# Ver_5.net
KiCad netlist of a schematic drawn in EAGLE
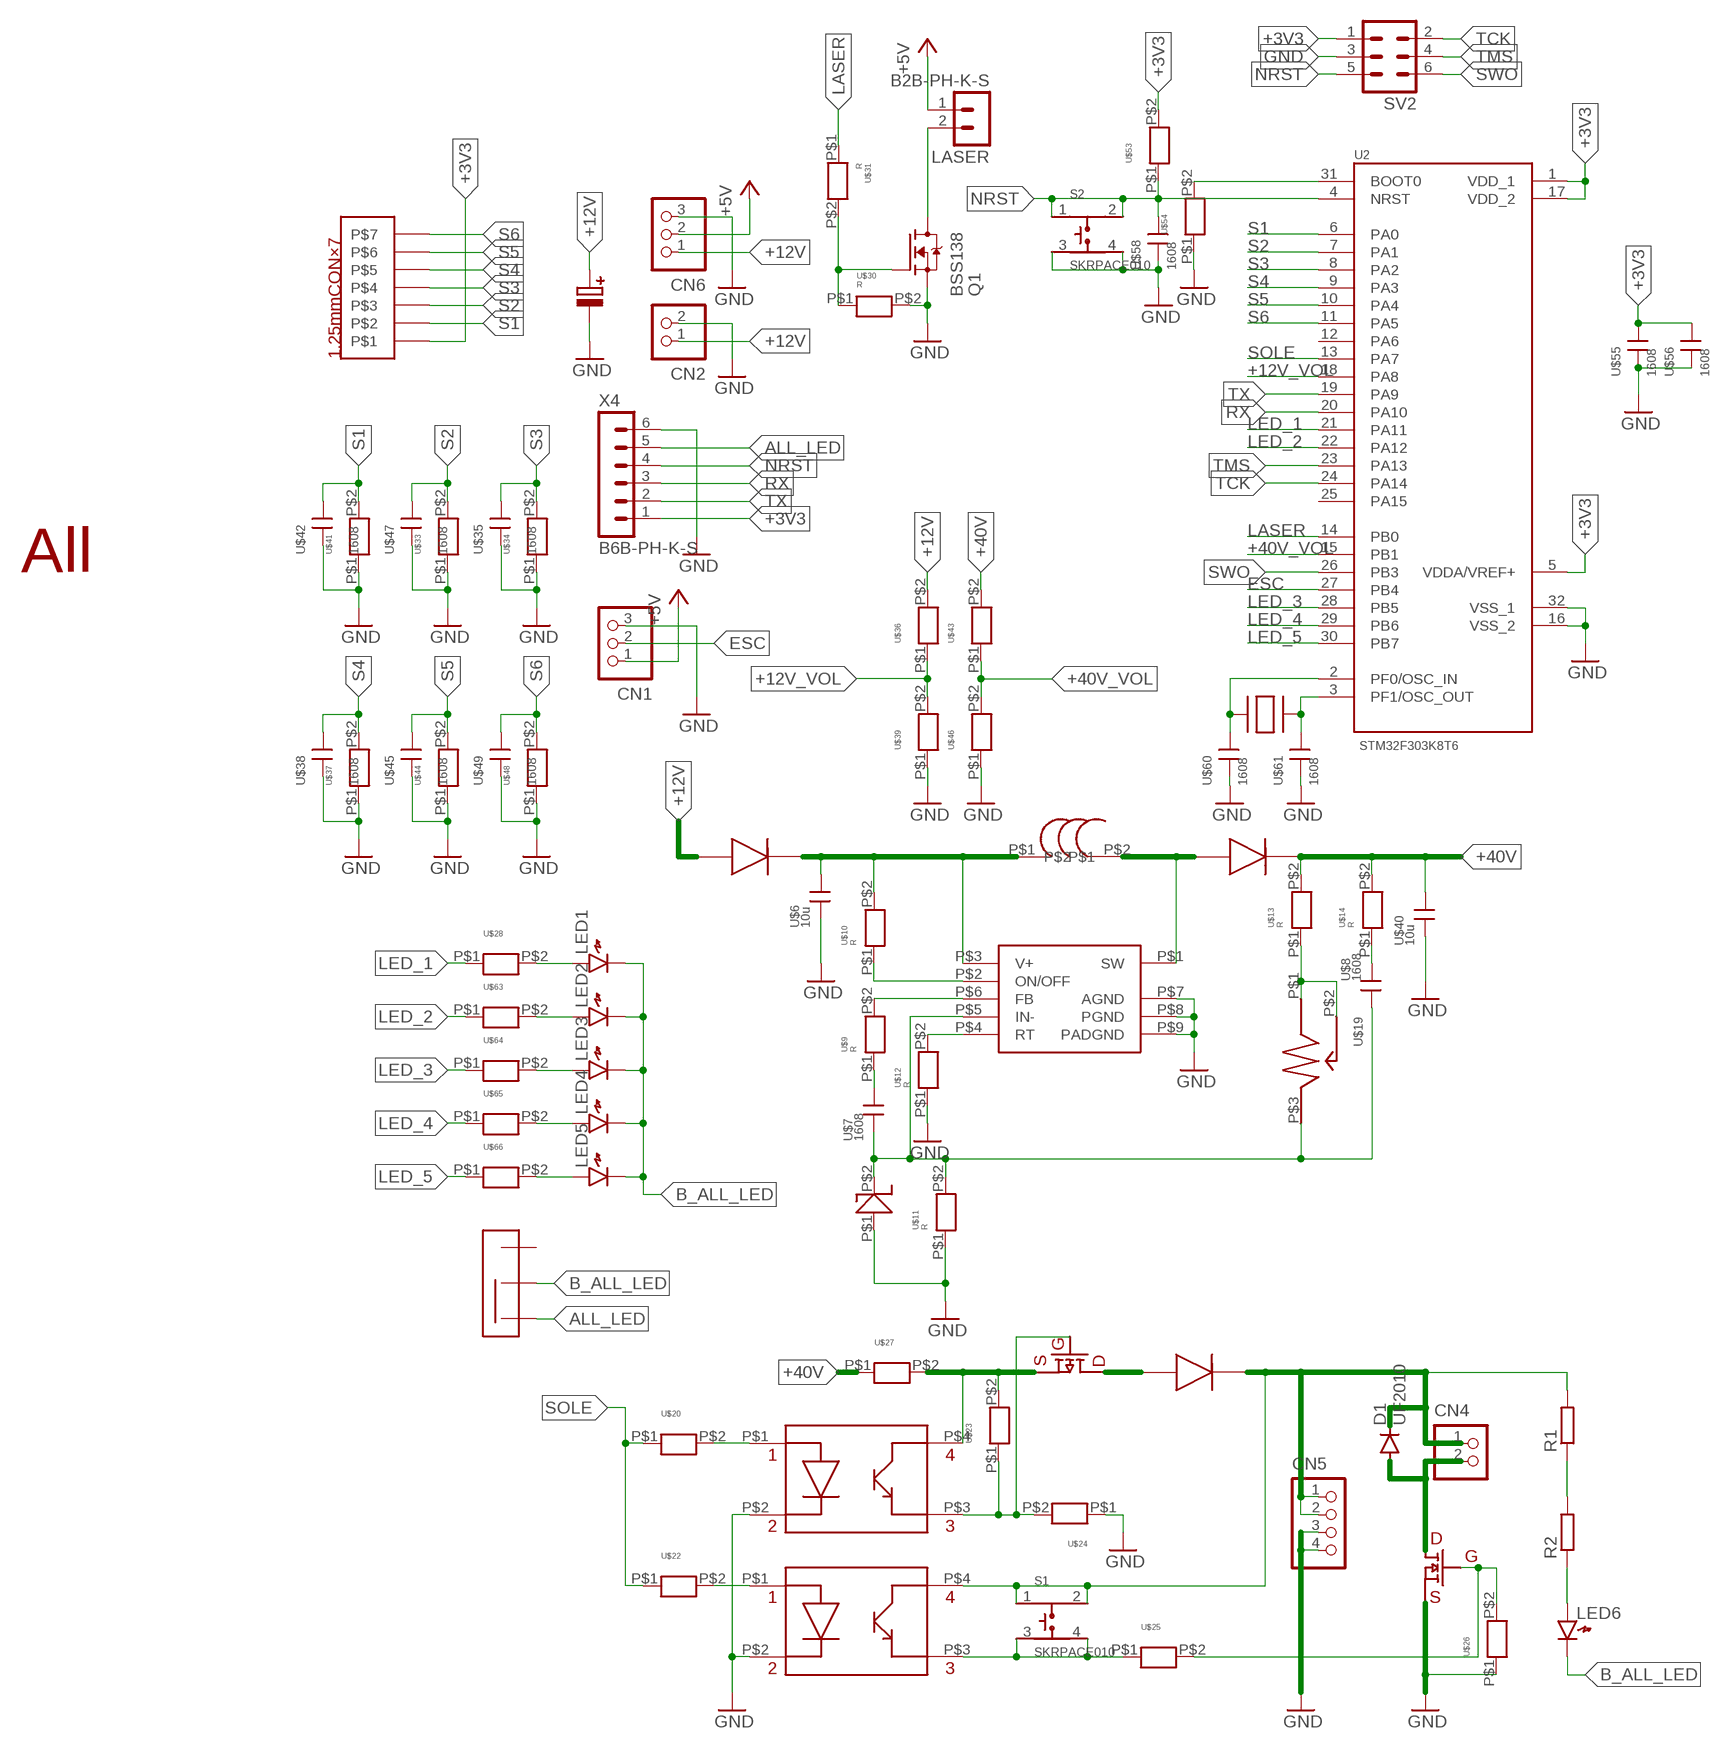
[diagram p0: schematic, sheet 1]
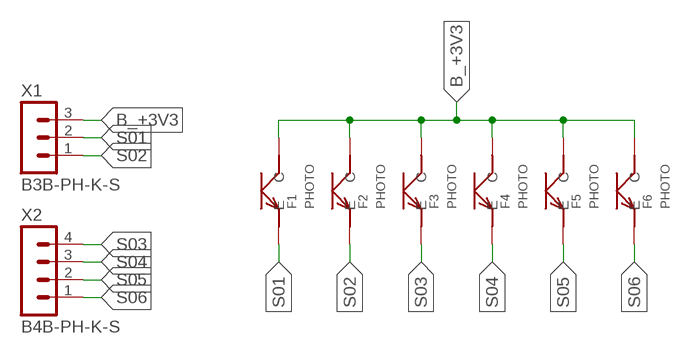
[diagram p1: schematic, sheet 2]

(export (version "E")
  (design (tool "Eeschema 10.0.6"))
  (components
    (comp (ref "F1")
      (value "PHOTO")
      (footprint "eagle-import:PHOTO")
      (libsource (lib "eagle-import") (part "PHOTO"))
    )
    (comp (ref "F2")
      (value "PHOTO")
      (footprint "eagle-import:PHOTO")
      (libsource (lib "eagle-import") (part "PHOTO"))
    )
    (comp (ref "F3")
      (value "PHOTO")
      (footprint "eagle-import:PHOTO")
      (libsource (lib "eagle-import") (part "PHOTO"))
    )
    (comp (ref "F4")
      (value "PHOTO")
      (footprint "eagle-import:PHOTO")
      (libsource (lib "eagle-import") (part "PHOTO"))
    )
    (comp (ref "F5")
      (value "PHOTO")
      (footprint "eagle-import:PHOTO")
      (libsource (lib "eagle-import") (part "PHOTO"))
    )
    (comp (ref "F6")
      (value "PHOTO")
      (footprint "eagle-import:PHOTO")
      (libsource (lib "eagle-import") (part "PHOTO"))
    )
    (comp (ref "X1")
      (value "B3B-PH-K-S")
      (footprint "eagle-import:B3B-PH-K-S")
      (libsource (lib "eagle-import") (part "B3B-PH-K-S"))
    )
    (comp (ref "X2")
      (value "B4B-PH-K-S")
      (footprint "eagle-import:B4B-PH-K-S")
      (libsource (lib "eagle-import") (part "B4B-PH-K-S"))
    )
    (comp (ref "CN1")
      (value "B3B-XH-A")
      (footprint "eagle-import:B3B-XH-A")
      (libsource (lib "eagle-import") (part "B3B-XH-A"))
    )
    (comp (ref "CN2")
      (value "B2B-XH-A")
      (footprint "eagle-import:B2B-XH-A")
      (libsource (lib "eagle-import") (part "B2B-XH-A"))
    )
    (comp (ref "CN4")
      (value "B2B-XH-A")
      (footprint "eagle-import:B2B-XH-A")
      (libsource (lib "eagle-import") (part "B2B-XH-A"))
    )
    (comp (ref "CN5")
      (value "B4B-XH-A")
      (footprint "eagle-import:B4B-XH-A")
      (libsource (lib "eagle-import") (part "B4B-XH-A"))
    )
    (comp (ref "CN6")
      (value "B3B-XH-A")
      (footprint "eagle-import:B3B-XH-A")
      (libsource (lib "eagle-import") (part "B3B-XH-A"))
    )
    (comp (ref "D1")
      (value "UF2010")
      (footprint "eagle-import:DO35-10")
      (libsource (lib "eagle-import") (part "1N4148DO35-10"))
    )
    (comp (ref "LASER")
      (value "B2B-PH-K-S")
      (footprint "eagle-import:B2B-PH-K-S")
      (libsource (lib "eagle-import") (part "B2B-PH-K-S"))
    )
    (comp (ref "LED1")
      (value "LED1608")
      (footprint "eagle-import:LED1608")
      (libsource (lib "eagle-import") (part "LED1608"))
    )
    (comp (ref "LED2")
      (value "LED1608")
      (footprint "eagle-import:LED1608")
      (libsource (lib "eagle-import") (part "LED1608"))
    )
    (comp (ref "LED3")
      (value "LED1608")
      (footprint "eagle-import:LED1608")
      (libsource (lib "eagle-import") (part "LED1608"))
    )
    (comp (ref "LED4")
      (value "LED1608")
      (footprint "eagle-import:LED1608")
      (libsource (lib "eagle-import") (part "LED1608"))
    )
    (comp (ref "LED5")
      (value "LED1608")
      (footprint "eagle-import:LED1608")
      (libsource (lib "eagle-import") (part "LED1608"))
    )
    (comp (ref "LED6")
      (value "LED1608")
      (footprint "eagle-import:LED1608")
      (libsource (lib "eagle-import") (part "LED1608"))
    )
    (comp (ref "Q1")
      (value "BSS138")
      (footprint "eagle-import:SOT23")
      (fields (field (name "MF") "Fairchild"))
      (libsource (lib "eagle-import") (part "BSS138"))
    )
    (comp (ref "R1")
      (value "R-EU_0207/12")
      (footprint "eagle-import:0207_12")
      (libsource (lib "eagle-import") (part "R-EU_0207/12"))
    )
    (comp (ref "R2")
      (value "R-EU_0207/12")
      (footprint "eagle-import:0207_12")
      (libsource (lib "eagle-import") (part "R-EU_0207/12"))
    )
    (comp (ref "S1")
      (value "SKRPACE010")
      (footprint "eagle-import:SW_SKRPACE010")
      (fields (field (name "MF") "ALPS"))
      (libsource (lib "eagle-import") (part "SKRPACE010"))
    )
    (comp (ref "S2")
      (value "SKRPACE010")
      (footprint "eagle-import:SW_SKRPACE010")
      (fields (field (name "MF") "ALPS"))
      (libsource (lib "eagle-import") (part "SKRPACE010"))
    )
    (comp (ref "SV2")
      (value "ML6")
      (footprint "eagle-import:ML6")
      (libsource (lib "eagle-import") (part "ML6"))
    )
    (comp (ref "U$1") (value "TD") (footprint "eagle-import:TD") (libsource (lib "eagle-import") (part "TD")))
    (comp (ref "U$2")
      (value "40V5A")
      (footprint "eagle-import:40V5A")
      (libsource (lib "eagle-import") (part "40V5A"))
    )
    (comp (ref "U$3")
      (value "40V5A")
      (footprint "eagle-import:40V5A")
      (libsource (lib "eagle-import") (part "40V5A"))
    )
    (comp (ref "U$4")
      (value "TLP291")
      (footprint "eagle-import:TPL291")
      (libsource (lib "eagle-import") (part "TLP291"))
    )
    (comp (ref "U$5")
      (value "NJW4131GM1")
      (footprint "eagle-import:NJW4131")
      (libsource (lib "eagle-import") (part "NJW4131GM1"))
    )
    (comp (ref "U$6")
      (value "10u")
      (footprint "eagle-import:CON")
      (libsource (lib "eagle-import") (part "1608"))
    )
    (comp (ref "U$7")
      (value "1608")
      (footprint "eagle-import:CON")
      (libsource (lib "eagle-import") (part "1608"))
    )
    (comp (ref "U$8")
      (value "1608")
      (footprint "eagle-import:CON")
      (libsource (lib "eagle-import") (part "1608"))
    )
    (comp (ref "U$9") (value "R") (footprint "eagle-import:1608") (libsource (lib "eagle-import") (part "R")))
    (comp (ref "U$10")
      (value "R")
      (footprint "eagle-import:1608")
      (libsource (lib "eagle-import") (part "R"))
    )
    (comp (ref "U$11")
      (value "R")
      (footprint "eagle-import:1608")
      (libsource (lib "eagle-import") (part "R"))
    )
    (comp (ref "U$12")
      (value "R")
      (footprint "eagle-import:1608")
      (libsource (lib "eagle-import") (part "R"))
    )
    (comp (ref "U$13")
      (value "R")
      (footprint "eagle-import:1608")
      (libsource (lib "eagle-import") (part "R"))
    )
    (comp (ref "U$14")
      (value "R")
      (footprint "eagle-import:1608")
      (libsource (lib "eagle-import") (part "R"))
    )
    (comp (ref "U$15")
      (value "TLP291")
      (footprint "eagle-import:TPL291")
      (libsource (lib "eagle-import") (part "TLP291"))
    )
    (comp (ref "U$16")
      (value "808")
      (footprint "eagle-import:808")
      (libsource (lib "eagle-import") (part "808"))
    )
    (comp (ref "U$17")
      (value "SSM6K8")
      (footprint "eagle-import:SSM6K8")
      (libsource (lib "eagle-import") (part "SSM6K8"))
    )
    (comp (ref "U$18")
      (value "40V5A")
      (footprint "eagle-import:40V5A")
      (libsource (lib "eagle-import") (part "40V5A"))
    )
    (comp (ref "U$19")
      (value "VR")
      (footprint "eagle-import:VR")
      (libsource (lib "eagle-import") (part "VR"))
    )
    (comp (ref "U$20")
      (value "R")
      (footprint "eagle-import:1608")
      (libsource (lib "eagle-import") (part "R"))
    )
    (comp (ref "U$21")
      (value "1MM7")
      (footprint "eagle-import:1MM7")
      (libsource (lib "eagle-import") (part "1MM7"))
    )
    (comp (ref "U$22")
      (value "R")
      (footprint "eagle-import:1608")
      (libsource (lib "eagle-import") (part "R"))
    )
    (comp (ref "U$23")
      (value "R")
      (footprint "eagle-import:1608")
      (libsource (lib "eagle-import") (part "R"))
    )
    (comp (ref "U$24")
      (value "R")
      (footprint "eagle-import:1608")
      (libsource (lib "eagle-import") (part "R"))
    )
    (comp (ref "U$25")
      (value "R")
      (footprint "eagle-import:1608")
      (libsource (lib "eagle-import") (part "R"))
    )
    (comp (ref "U$26")
      (value "R")
      (footprint "eagle-import:1608")
      (libsource (lib "eagle-import") (part "R"))
    )
    (comp (ref "U$27")
      (value "R")
      (footprint "eagle-import:1608")
      (libsource (lib "eagle-import") (part "R"))
    )
    (comp (ref "U$28")
      (value "R")
      (footprint "eagle-import:1608")
      (libsource (lib "eagle-import") (part "R"))
    )
    (comp (ref "U$29")
      (value "ALL")
      (footprint "eagle-import:ALL")
      (libsource (lib "eagle-import") (part "ALL"))
    )
    (comp (ref "U$30")
      (value "R")
      (footprint "eagle-import:1608")
      (libsource (lib "eagle-import") (part "R"))
    )
    (comp (ref "U$31")
      (value "R")
      (footprint "eagle-import:1608")
      (libsource (lib "eagle-import") (part "R"))
    )
    (comp (ref "U$33")
      (value "R")
      (footprint "eagle-import:1608")
      (libsource (lib "eagle-import") (part "R"))
    )
    (comp (ref "U$34")
      (value "R")
      (footprint "eagle-import:1608")
      (libsource (lib "eagle-import") (part "R"))
    )
    (comp (ref "U$35")
      (value "1608")
      (footprint "eagle-import:CON")
      (libsource (lib "eagle-import") (part "1608"))
    )
    (comp (ref "U$36")
      (value "R")
      (footprint "eagle-import:1608")
      (libsource (lib "eagle-import") (part "R"))
    )
    (comp (ref "U$37")
      (value "R")
      (footprint "eagle-import:1608")
      (libsource (lib "eagle-import") (part "R"))
    )
    (comp (ref "U$38")
      (value "1608")
      (footprint "eagle-import:CON")
      (libsource (lib "eagle-import") (part "1608"))
    )
    (comp (ref "U$39")
      (value "R")
      (footprint "eagle-import:1608")
      (libsource (lib "eagle-import") (part "R"))
    )
    (comp (ref "U$40")
      (value "10u")
      (footprint "eagle-import:CON")
      (libsource (lib "eagle-import") (part "1608"))
    )
    (comp (ref "U$41")
      (value "R")
      (footprint "eagle-import:1608")
      (libsource (lib "eagle-import") (part "R"))
    )
    (comp (ref "U$42")
      (value "1608")
      (footprint "eagle-import:CON")
      (libsource (lib "eagle-import") (part "1608"))
    )
    (comp (ref "U$43")
      (value "R")
      (footprint "eagle-import:1608")
      (libsource (lib "eagle-import") (part "R"))
    )
    (comp (ref "U$44")
      (value "R")
      (footprint "eagle-import:1608")
      (libsource (lib "eagle-import") (part "R"))
    )
    (comp (ref "U$45")
      (value "1608")
      (footprint "eagle-import:CON")
      (libsource (lib "eagle-import") (part "1608"))
    )
    (comp (ref "U$46")
      (value "R")
      (footprint "eagle-import:1608")
      (libsource (lib "eagle-import") (part "R"))
    )
    (comp (ref "U$47")
      (value "1608")
      (footprint "eagle-import:CON")
      (libsource (lib "eagle-import") (part "1608"))
    )
    (comp (ref "U$48")
      (value "R")
      (footprint "eagle-import:1608")
      (libsource (lib "eagle-import") (part "R"))
    )
    (comp (ref "U$49")
      (value "1608")
      (footprint "eagle-import:CON")
      (libsource (lib "eagle-import") (part "1608"))
    )
    (comp (ref "U$50") (value "I") (footprint "eagle-import:I") (libsource (lib "eagle-import") (part "I")))
    (comp (ref "U$53")
      (value "R")
      (footprint "eagle-import:1608")
      (libsource (lib "eagle-import") (part "R"))
    )
    (comp (ref "U$54")
      (value "R")
      (footprint "eagle-import:1608")
      (libsource (lib "eagle-import") (part "R"))
    )
    (comp (ref "U$55")
      (value "1608")
      (footprint "eagle-import:CON")
      (libsource (lib "eagle-import") (part "1608"))
    )
    (comp (ref "U$56")
      (value "1608")
      (footprint "eagle-import:CON")
      (libsource (lib "eagle-import") (part "1608"))
    )
    (comp (ref "U$58")
      (value "1608")
      (footprint "eagle-import:CON")
      (libsource (lib "eagle-import") (part "1608"))
    )
    (comp (ref "U$59")
      (value "SUISYOU")
      (footprint "eagle-import:水晶")
      (libsource (lib "eagle-import") (part "SUISYOU"))
    )
    (comp (ref "U$60")
      (value "1608")
      (footprint "eagle-import:CON")
      (libsource (lib "eagle-import") (part "1608"))
    )
    (comp (ref "U$61")
      (value "1608")
      (footprint "eagle-import:CON")
      (libsource (lib "eagle-import") (part "1608"))
    )
    (comp (ref "U$62")
      (value "25V100")
      (footprint "eagle-import:25V100")
      (libsource (lib "eagle-import") (part "25V100"))
    )
    (comp (ref "U$63")
      (value "R")
      (footprint "eagle-import:1608")
      (libsource (lib "eagle-import") (part "R"))
    )
    (comp (ref "U$64")
      (value "R")
      (footprint "eagle-import:1608")
      (libsource (lib "eagle-import") (part "R"))
    )
    (comp (ref "U$65")
      (value "R")
      (footprint "eagle-import:1608")
      (libsource (lib "eagle-import") (part "R"))
    )
    (comp (ref "U$66")
      (value "R")
      (footprint "eagle-import:1608")
      (libsource (lib "eagle-import") (part "R"))
    )
    (comp (ref "U$67")
      (value "SSW")
      (footprint "eagle-import:SSW")
      (libsource (lib "eagle-import") (part "SSW"))
    )
    (comp (ref "U2")
      (value "STM32F303K8T6")
      (footprint "eagle-import:QFP80P900X900X160-32N")
      (fields (field (name "MF") "STMicroelectronics"))
      (libsource (lib "eagle-import") (part "STM32F303K8T6"))
    )
    (comp (ref "X4")
      (value "B6B-PH-K-S")
      (footprint "eagle-import:B6B-PH-K-S")
      (libsource (lib "eagle-import") (part "B6B-PH-K-S"))
    )
  )
  (nets
    (net (code "1") (name "+3V3") (class "Default")
      (node (ref "SV2") (pin "1") (pinfunction "1_1") (pintype "passive"))
      (node (ref "U$21") (pin "P$1") (pinfunction "P$1_P$1") (pintype "bidirectional"))
      (node (ref "U$53") (pin "P$2") (pinfunction "P$2_P$2") (pintype "bidirectional"))
      (node (ref "U$55") (pin "P$1") (pinfunction "1_P$1") (pintype "bidirectional"))
      (node (ref "U$56") (pin "P$1") (pinfunction "1_P$1") (pintype "bidirectional"))
      (node (ref "U2") (pin "1") (pinfunction "VDD_1_1") (pintype "power_in"))
      (node (ref "U2") (pin "17") (pinfunction "VDD_2_17") (pintype "power_in"))
      (node (ref "U2") (pin "5") (pinfunction "VDDA/VREF+_5") (pintype "power_in"))
      (node (ref "X4") (pin "1") (pinfunction "1_1") (pintype "passive"))
    )
    (net (code "2") (name "+5V") (class "Default")
      (node (ref "CN1") (pin "1") (pinfunction "1_1") (pintype "passive"))
      (node (ref "CN6") (pin "2") (pinfunction "2_2") (pintype "passive"))
      (node (ref "LASER") (pin "1") (pinfunction "1_1") (pintype "passive"))
    )
    (net (code "3") (name "+12V") (class "Default")
      (node (ref "CN2") (pin "1") (pinfunction "1_1") (pintype "passive"))
      (node (ref "CN6") (pin "1") (pinfunction "1_1") (pintype "passive"))
      (node (ref "U$3") (pin "P$1") (pinfunction "P$1_P$1") (pintype "bidirectional"))
      (node (ref "U$36") (pin "P$2") (pinfunction "P$2_P$2") (pintype "bidirectional"))
      (node (ref "U$62") (pin "P$1") (pinfunction "P$1_P$1") (pintype "bidirectional"))
    )
    (net (code "4") (name "+12V_VOL") (class "Default")
      (node (ref "U$36") (pin "P$1") (pinfunction "P$1_P$1") (pintype "bidirectional"))
      (node (ref "U$39") (pin "P$2") (pinfunction "P$2_P$2") (pintype "bidirectional"))
      (node (ref "U2") (pin "18") (pinfunction "PA8_18") (pintype "bidirectional"))
    )
    (net (code "5") (name "+40V") (class "Default")
      (node (ref "U$13") (pin "P$2") (pinfunction "P$2_P$2") (pintype "bidirectional"))
      (node (ref "U$14") (pin "P$2") (pinfunction "P$2_P$2") (pintype "bidirectional"))
      (node (ref "U$2") (pin "P$2") (pinfunction "P$2_P$2") (pintype "bidirectional"))
      (node (ref "U$27") (pin "P$1") (pinfunction "P$1_P$1") (pintype "bidirectional"))
      (node (ref "U$40") (pin "P$1") (pinfunction "1_P$1") (pintype "bidirectional"))
      (node (ref "U$43") (pin "P$2") (pinfunction "P$2_P$2") (pintype "bidirectional"))
    )
    (net (code "6") (name "+40V_VOL") (class "Default")
      (node (ref "U$43") (pin "P$1") (pinfunction "P$1_P$1") (pintype "bidirectional"))
      (node (ref "U$46") (pin "P$2") (pinfunction "P$2_P$2") (pintype "bidirectional"))
      (node (ref "U2") (pin "15") (pinfunction "PB1_15") (pintype "bidirectional"))
    )
    (net (code "7") (name "ALL_LED") (class "Default")
      (node (ref "U$67") (pin "P$1") (pinfunction "P$1_P$1") (pintype "bidirectional"))
      (node (ref "X4") (pin "5") (pinfunction "5_5") (pintype "passive"))
    )
    (net (code "8") (name "B_+3V3") (class "Default")
      (node (ref "F1") (pin "P$1") (pinfunction "C_P$1") (pintype "bidirectional"))
      (node (ref "F2") (pin "P$1") (pinfunction "C_P$1") (pintype "bidirectional"))
      (node (ref "F3") (pin "P$1") (pinfunction "C_P$1") (pintype "bidirectional"))
      (node (ref "F4") (pin "P$1") (pinfunction "C_P$1") (pintype "bidirectional"))
      (node (ref "F5") (pin "P$1") (pinfunction "C_P$1") (pintype "bidirectional"))
      (node (ref "F6") (pin "P$1") (pinfunction "C_P$1") (pintype "bidirectional"))
      (node (ref "X1") (pin "3") (pinfunction "3_3") (pintype "passive"))
    )
    (net (code "9") (name "B_ALL_LED") (class "Default")
      (node (ref "LED1") (pin "K") (pinfunction "K_K") (pintype "passive"))
      (node (ref "LED2") (pin "K") (pinfunction "K_K") (pintype "passive"))
      (node (ref "LED3") (pin "K") (pinfunction "K_K") (pintype "passive"))
      (node (ref "LED4") (pin "K") (pinfunction "K_K") (pintype "passive"))
      (node (ref "LED5") (pin "K") (pinfunction "K_K") (pintype "passive"))
      (node (ref "LED6") (pin "K") (pinfunction "K_K") (pintype "passive"))
      (node (ref "U$67") (pin "P$3") (pinfunction "P$2_P$3") (pintype "bidirectional"))
    )
    (net (code "10") (name "ESC") (class "Default")
      (node (ref "CN1") (pin "2") (pinfunction "2_2") (pintype "passive"))
      (node (ref "U2") (pin "27") (pinfunction "PB4_27") (pintype "bidirectional"))
    )
    (net (code "11") (name "GND") (class "Default")
      (node (ref "CN1") (pin "3") (pinfunction "3_3") (pintype "passive"))
      (node (ref "CN2") (pin "2") (pinfunction "2_2") (pintype "passive"))
      (node (ref "CN5") (pin "3") (pinfunction "3_3") (pintype "passive"))
      (node (ref "CN5") (pin "4") (pinfunction "4_4") (pintype "passive"))
      (node (ref "CN6") (pin "3") (pinfunction "3_3") (pintype "passive"))
      (node (ref "Q1") (pin "2") (pinfunction "S_2") (pintype "passive"))
      (node (ref "S2") (pin "3") (pinfunction "3_3") (pintype "bidirectional"))
      (node (ref "S2") (pin "4") (pinfunction "4_4") (pintype "bidirectional"))
      (node (ref "SV2") (pin "3") (pinfunction "3_3") (pintype "passive"))
      (node (ref "U$1") (pin "P$1") (pinfunction "P$1_P$1") (pintype "bidirectional"))
      (node (ref "U$11") (pin "P$1") (pinfunction "P$1_P$1") (pintype "bidirectional"))
      (node (ref "U$12") (pin "P$1") (pinfunction "P$1_P$1") (pintype "bidirectional"))
      (node (ref "U$15") (pin "P$2") (pinfunction "2_P$2") (pintype "bidirectional"))
      (node (ref "U$17") (pin "S") (pinfunction "S_S") (pintype "bidirectional"))
      (node (ref "U$24") (pin "P$1") (pinfunction "P$1_P$1") (pintype "bidirectional"))
      (node (ref "U$26") (pin "P$1") (pinfunction "P$1_P$1") (pintype "bidirectional"))
      (node (ref "U$30") (pin "P$2") (pinfunction "P$2_P$2") (pintype "bidirectional"))
      (node (ref "U$33") (pin "P$1") (pinfunction "P$1_P$1") (pintype "bidirectional"))
      (node (ref "U$34") (pin "P$1") (pinfunction "P$1_P$1") (pintype "bidirectional"))
      (node (ref "U$35") (pin "P$2") (pinfunction "2_P$2") (pintype "bidirectional"))
      (node (ref "U$37") (pin "P$1") (pinfunction "P$1_P$1") (pintype "bidirectional"))
      (node (ref "U$38") (pin "P$2") (pinfunction "2_P$2") (pintype "bidirectional"))
      (node (ref "U$39") (pin "P$1") (pinfunction "P$1_P$1") (pintype "bidirectional"))
      (node (ref "U$4") (pin "P$2") (pinfunction "2_P$2") (pintype "bidirectional"))
      (node (ref "U$40") (pin "P$2") (pinfunction "2_P$2") (pintype "bidirectional"))
      (node (ref "U$41") (pin "P$1") (pinfunction "P$1_P$1") (pintype "bidirectional"))
      (node (ref "U$42") (pin "P$2") (pinfunction "2_P$2") (pintype "bidirectional"))
      (node (ref "U$44") (pin "P$1") (pinfunction "P$1_P$1") (pintype "bidirectional"))
      (node (ref "U$45") (pin "P$2") (pinfunction "2_P$2") (pintype "bidirectional"))
      (node (ref "U$46") (pin "P$1") (pinfunction "P$1_P$1") (pintype "bidirectional"))
      (node (ref "U$47") (pin "P$2") (pinfunction "2_P$2") (pintype "bidirectional"))
      (node (ref "U$48") (pin "P$1") (pinfunction "P$1_P$1") (pintype "bidirectional"))
      (node (ref "U$49") (pin "P$2") (pinfunction "2_P$2") (pintype "bidirectional"))
      (node (ref "U$5") (pin "P$7") (pinfunction "AGND_P$7") (pintype "bidirectional"))
      (node (ref "U$5") (pin "P$8") (pinfunction "PGND_P$8") (pintype "bidirectional"))
      (node (ref "U$5") (pin "P$9") (pinfunction "PADGND_P$9") (pintype "bidirectional"))
      (node (ref "U$54") (pin "P$1") (pinfunction "P$1_P$1") (pintype "bidirectional"))
      (node (ref "U$55") (pin "P$2") (pinfunction "2_P$2") (pintype "bidirectional"))
      (node (ref "U$56") (pin "P$2") (pinfunction "2_P$2") (pintype "bidirectional"))
      (node (ref "U$58") (pin "P$2") (pinfunction "2_P$2") (pintype "bidirectional"))
      (node (ref "U$6") (pin "P$2") (pinfunction "2_P$2") (pintype "bidirectional"))
      (node (ref "U$60") (pin "P$2") (pinfunction "2_P$2") (pintype "bidirectional"))
      (node (ref "U$61") (pin "P$2") (pinfunction "2_P$2") (pintype "bidirectional"))
      (node (ref "U$62") (pin "P$2") (pinfunction "P$2_P$2") (pintype "bidirectional"))
      (node (ref "U2") (pin "16") (pinfunction "VSS_2_16") (pintype "power_in"))
      (node (ref "U2") (pin "32") (pinfunction "VSS_1_32") (pintype "power_in"))
      (node (ref "X4") (pin "6") (pinfunction "6_6") (pintype "passive"))
    )
    (net (code "12") (name "LASER") (class "Default")
      (node (ref "U$31") (pin "P$1") (pinfunction "P$1_P$1") (pintype "bidirectional"))
      (node (ref "U2") (pin "14") (pinfunction "PB0_14") (pintype "bidirectional"))
    )
    (net (code "13") (name "LED_1") (class "Default")
      (node (ref "U$28") (pin "P$1") (pinfunction "P$1_P$1") (pintype "bidirectional"))
      (node (ref "U2") (pin "21") (pinfunction "PA11_21") (pintype "bidirectional"))
    )
    (net (code "14") (name "LED_2") (class "Default")
      (node (ref "U$63") (pin "P$1") (pinfunction "P$1_P$1") (pintype "bidirectional"))
      (node (ref "U2") (pin "22") (pinfunction "PA12_22") (pintype "bidirectional"))
    )
    (net (code "15") (name "LED_3") (class "Default")
      (node (ref "U$64") (pin "P$1") (pinfunction "P$1_P$1") (pintype "bidirectional"))
      (node (ref "U2") (pin "28") (pinfunction "PB5_28") (pintype "bidirectional"))
    )
    (net (code "16") (name "LED_4") (class "Default")
      (node (ref "U$65") (pin "P$1") (pinfunction "P$1_P$1") (pintype "bidirectional"))
      (node (ref "U2") (pin "29") (pinfunction "PB6_29") (pintype "bidirectional"))
    )
    (net (code "17") (name "LED_5") (class "Default")
      (node (ref "U$66") (pin "P$1") (pinfunction "P$1_P$1") (pintype "bidirectional"))
      (node (ref "U2") (pin "30") (pinfunction "PB7_30") (pintype "bidirectional"))
    )
    (net (code "18") (name "NRST") (class "Default")
      (node (ref "S2") (pin "1") (pinfunction "1_1") (pintype "bidirectional"))
      (node (ref "S2") (pin "2") (pinfunction "2_2") (pintype "bidirectional"))
      (node (ref "SV2") (pin "5") (pinfunction "5_5") (pintype "passive"))
      (node (ref "U$53") (pin "P$1") (pinfunction "P$1_P$1") (pintype "bidirectional"))
      (node (ref "U$58") (pin "P$1") (pinfunction "1_P$1") (pintype "bidirectional"))
      (node (ref "U2") (pin "4") (pinfunction "NRST_4") (pintype "bidirectional"))
      (node (ref "X4") (pin "4") (pinfunction "4_4") (pintype "passive"))
    )
    (net (code "19") (name "Net-(CN4-Pad2)") (class "Default")
      (node (ref "CN4") (pin "2") (pinfunction "2_2") (pintype "passive"))
      (node (ref "D1") (pin "A") (pinfunction "A_A") (pintype "passive"))
      (node (ref "U$17") (pin "D") (pinfunction "D_D") (pintype "bidirectional"))
      (node (ref "U$17") (pin "DD") (pinfunction "D_DD") (pintype "bidirectional"))
      (node (ref "U$17") (pin "DDD") (pinfunction "D_DDD") (pintype "bidirectional"))
      (node (ref "U$17") (pin "DDDD") (pinfunction "D_DDDD") (pintype "bidirectional"))
    )
    (net (code "20") (name "Net-(LED1-PadA)") (class "Default")
      (node (ref "LED1") (pin "A") (pinfunction "A_A") (pintype "passive"))
      (node (ref "U$28") (pin "P$2") (pinfunction "P$2_P$2") (pintype "bidirectional"))
    )
    (net (code "21") (name "Net-(LED2-PadA)") (class "Default")
      (node (ref "LED2") (pin "A") (pinfunction "A_A") (pintype "passive"))
      (node (ref "U$63") (pin "P$2") (pinfunction "P$2_P$2") (pintype "bidirectional"))
    )
    (net (code "22") (name "Net-(LED3-PadA)") (class "Default")
      (node (ref "LED3") (pin "A") (pinfunction "A_A") (pintype "passive"))
      (node (ref "U$64") (pin "P$2") (pinfunction "P$2_P$2") (pintype "bidirectional"))
    )
    (net (code "23") (name "Net-(LED4-PadA)") (class "Default")
      (node (ref "LED4") (pin "A") (pinfunction "A_A") (pintype "passive"))
      (node (ref "U$65") (pin "P$2") (pinfunction "P$2_P$2") (pintype "bidirectional"))
    )
    (net (code "24") (name "Net-(LED5-PadA)") (class "Default")
      (node (ref "LED5") (pin "A") (pinfunction "A_A") (pintype "passive"))
      (node (ref "U$66") (pin "P$2") (pinfunction "P$2_P$2") (pintype "bidirectional"))
    )
    (net (code "25") (name "Net-(LED6-PadA)") (class "Default")
      (node (ref "LED6") (pin "A") (pinfunction "A_A") (pintype "passive"))
      (node (ref "R2") (pin "1") (pinfunction "1_1") (pintype "passive"))
    )
    (net (code "26") (name "Net-(Q1-D)") (class "Default")
      (node (ref "LASER") (pin "2") (pinfunction "2_2") (pintype "passive"))
      (node (ref "Q1") (pin "3") (pinfunction "D_3") (pintype "passive"))
    )
    (net (code "27") (name "Net-(Q1-G)") (class "Default")
      (node (ref "Q1") (pin "1") (pinfunction "G_1") (pintype "passive"))
      (node (ref "U$30") (pin "P$1") (pinfunction "P$1_P$1") (pintype "bidirectional"))
      (node (ref "U$31") (pin "P$2") (pinfunction "P$2_P$2") (pintype "bidirectional"))
    )
    (net (code "28") (name "Net-(R1-Pad1)") (class "Default")
      (node (ref "R1") (pin "1") (pinfunction "1_1") (pintype "passive"))
      (node (ref "R2") (pin "2") (pinfunction "2_2") (pintype "passive"))
    )
    (net (code "29") (name "Net-(U$4-1)") (class "Default")
      (node (ref "U$20") (pin "P$2") (pinfunction "P$2_P$2") (pintype "bidirectional"))
      (node (ref "U$4") (pin "P$1") (pinfunction "1_P$1") (pintype "bidirectional"))
    )
    (net (code "30") (name "Net-(U$4-3)") (class "Default")
      (node (ref "U$16") (pin "G") (pinfunction "G_G") (pintype "bidirectional"))
      (node (ref "U$23") (pin "P$1") (pinfunction "P$1_P$1") (pintype "bidirectional"))
      (node (ref "U$24") (pin "P$2") (pinfunction "P$2_P$2") (pintype "bidirectional"))
      (node (ref "U$4") (pin "P$3") (pinfunction "3_P$3") (pintype "bidirectional"))
    )
    (net (code "31") (name "Net-(U$4-4)") (class "Default")
      (node (ref "U$16") (pin "S") (pinfunction "S_S") (pintype "bidirectional"))
      (node (ref "U$23") (pin "P$2") (pinfunction "P$2_P$2") (pintype "bidirectional"))
      (node (ref "U$27") (pin "P$2") (pinfunction "P$2_P$2") (pintype "bidirectional"))
      (node (ref "U$4") (pin "P$4") (pinfunction "4_P$4") (pintype "bidirectional"))
    )
    (net (code "32") (name "Net-(U$5-FB)") (class "Default")
      (node (ref "U$5") (pin "P$6") (pinfunction "FB_P$6") (pintype "bidirectional"))
      (node (ref "U$9") (pin "P$2") (pinfunction "P$2_P$2") (pintype "bidirectional"))
    )
    (net (code "33") (name "Net-(U$5-IN-)") (class "Default")
      (node (ref "U$1") (pin "P$2") (pinfunction "P$2_P$2") (pintype "bidirectional"))
      (node (ref "U$11") (pin "P$2") (pinfunction "P$2_P$2") (pintype "bidirectional"))
      (node (ref "U$19") (pin "P$3") (pinfunction "P$3_P$3") (pintype "bidirectional"))
      (node (ref "U$5") (pin "P$5") (pinfunction "IN-_P$5") (pintype "bidirectional"))
      (node (ref "U$7") (pin "P$2") (pinfunction "2_P$2") (pintype "bidirectional"))
      (node (ref "U$8") (pin "P$2") (pinfunction "2_P$2") (pintype "bidirectional"))
    )
    (net (code "34") (name "Net-(U$5-ON{slash}OFF)") (class "Default")
      (node (ref "U$10") (pin "P$1") (pinfunction "P$1_P$1") (pintype "bidirectional"))
      (node (ref "U$5") (pin "P$2") (pinfunction "ON/OFF_P$2") (pintype "bidirectional"))
    )
    (net (code "35") (name "Net-(U$5-RT)") (class "Default")
      (node (ref "U$12") (pin "P$2") (pinfunction "P$2_P$2") (pintype "bidirectional"))
      (node (ref "U$5") (pin "P$4") (pinfunction "RT_P$4") (pintype "bidirectional"))
    )
    (net (code "36") (name "Net-(U$5-SW)") (class "Default")
      (node (ref "U$2") (pin "P$1") (pinfunction "P$1_P$1") (pintype "bidirectional"))
      (node (ref "U$5") (pin "P$1") (pinfunction "SW_P$1") (pintype "bidirectional"))
      (node (ref "U$50") (pin "P$2") (pinfunction "P$2_P$2") (pintype "bidirectional"))
    )
    (net (code "37") (name "Net-(U$5-V+)") (class "Default")
      (node (ref "U$10") (pin "P$2") (pinfunction "P$2_P$2") (pintype "bidirectional"))
      (node (ref "U$3") (pin "P$2") (pinfunction "P$2_P$2") (pintype "bidirectional"))
      (node (ref "U$5") (pin "P$3") (pinfunction "V+_P$3") (pintype "bidirectional"))
      (node (ref "U$50") (pin "P$1") (pinfunction "P$1_P$1") (pintype "bidirectional"))
      (node (ref "U$6") (pin "P$1") (pinfunction "1_P$1") (pintype "bidirectional"))
    )
    (net (code "38") (name "Net-(U$7-1)") (class "Default")
      (node (ref "U$7") (pin "P$1") (pinfunction "1_P$1") (pintype "bidirectional"))
      (node (ref "U$9") (pin "P$1") (pinfunction "P$1_P$1") (pintype "bidirectional"))
    )
    (net (code "39") (name "Net-(U$8-1)") (class "Default")
      (node (ref "U$14") (pin "P$1") (pinfunction "P$1_P$1") (pintype "bidirectional"))
      (node (ref "U$8") (pin "P$1") (pinfunction "1_P$1") (pintype "bidirectional"))
    )
    (net (code "40") (name "Net-(U$13-PadP$1)") (class "Default")
      (node (ref "U$13") (pin "P$1") (pinfunction "P$1_P$1") (pintype "bidirectional"))
      (node (ref "U$19") (pin "P$1") (pinfunction "P$1_P$1") (pintype "bidirectional"))
      (node (ref "U$19") (pin "P$2") (pinfunction "P$2_P$2") (pintype "bidirectional"))
    )
    (net (code "41") (name "Net-(U$15-1)") (class "Default")
      (node (ref "U$15") (pin "P$1") (pinfunction "1_P$1") (pintype "bidirectional"))
      (node (ref "U$22") (pin "P$2") (pinfunction "P$2_P$2") (pintype "bidirectional"))
    )
    (net (code "42") (name "Net-(U$15-3)") (class "Default")
      (node (ref "S1") (pin "3") (pinfunction "3_3") (pintype "bidirectional"))
      (node (ref "S1") (pin "4") (pinfunction "4_4") (pintype "bidirectional"))
      (node (ref "U$15") (pin "P$3") (pinfunction "3_P$3") (pintype "bidirectional"))
      (node (ref "U$25") (pin "P$1") (pinfunction "P$1_P$1") (pintype "bidirectional"))
    )
    (net (code "43") (name "Net-(U$15-4)") (class "Default")
      (node (ref "CN4") (pin "1") (pinfunction "1_1") (pintype "passive"))
      (node (ref "CN5") (pin "1") (pinfunction "1_1") (pintype "passive"))
      (node (ref "CN5") (pin "2") (pinfunction "2_2") (pintype "passive"))
      (node (ref "D1") (pin "C") (pinfunction "C_C") (pintype "passive"))
      (node (ref "R1") (pin "2") (pinfunction "2_2") (pintype "passive"))
      (node (ref "S1") (pin "1") (pinfunction "1_1") (pintype "bidirectional"))
      (node (ref "S1") (pin "2") (pinfunction "2_2") (pintype "bidirectional"))
      (node (ref "U$15") (pin "P$4") (pinfunction "4_P$4") (pintype "bidirectional"))
      (node (ref "U$18") (pin "P$2") (pinfunction "P$2_P$2") (pintype "bidirectional"))
    )
    (net (code "44") (name "Net-(U$16-D-PadDD)") (class "Default")
      (node (ref "U$16") (pin "D") (pinfunction "D_D") (pintype "bidirectional"))
      (node (ref "U$16") (pin "DD") (pinfunction "D_DD") (pintype "bidirectional"))
      (node (ref "U$16") (pin "DDD") (pinfunction "D_DDD") (pintype "bidirectional"))
      (node (ref "U$16") (pin "DDDD") (pinfunction "D_DDDD") (pintype "bidirectional"))
      (node (ref "U$18") (pin "P$1") (pinfunction "P$1_P$1") (pintype "bidirectional"))
    )
    (net (code "45") (name "Net-(U$17-PadG)") (class "Default")
      (node (ref "U$17") (pin "G") (pinfunction "G_G") (pintype "bidirectional"))
      (node (ref "U$25") (pin "P$2") (pinfunction "P$2_P$2") (pintype "bidirectional"))
      (node (ref "U$26") (pin "P$2") (pinfunction "P$2_P$2") (pintype "bidirectional"))
    )
    (net (code "46") (name "Net-(U$60-1)") (class "Default")
      (node (ref "U$59") (pin "P$1") (pinfunction "P$1_P$1") (pintype "bidirectional"))
      (node (ref "U$60") (pin "P$1") (pinfunction "1_P$1") (pintype "bidirectional"))
      (node (ref "U2") (pin "2") (pinfunction "PF0/OSC_IN_2") (pintype "bidirectional"))
    )
    (net (code "47") (name "Net-(U$61-1)") (class "Default")
      (node (ref "U$59") (pin "P$2") (pinfunction "P$2_P$2") (pintype "bidirectional"))
      (node (ref "U$61") (pin "P$1") (pinfunction "1_P$1") (pintype "bidirectional"))
      (node (ref "U2") (pin "3") (pinfunction "PF1/OSC_OUT_3") (pintype "bidirectional"))
    )
    (net (code "48") (name "Net-(U2-BOOT0)") (class "Default")
      (node (ref "U$54") (pin "P$2") (pinfunction "P$2_P$2") (pintype "bidirectional"))
      (node (ref "U2") (pin "31") (pinfunction "BOOT0_31") (pintype "input"))
    )
    (net (code "49") (name "RX") (class "Default")
      (node (ref "U2") (pin "20") (pinfunction "PA10_20") (pintype "bidirectional"))
      (node (ref "X4") (pin "3") (pinfunction "3_3") (pintype "passive"))
    )
    (net (code "50") (name "S1") (class "Default")
      (node (ref "U$21") (pin "P$2") (pinfunction "P$2_P$2") (pintype "bidirectional"))
      (node (ref "U$41") (pin "P$2") (pinfunction "P$2_P$2") (pintype "bidirectional"))
      (node (ref "U$42") (pin "P$1") (pinfunction "1_P$1") (pintype "bidirectional"))
      (node (ref "U2") (pin "6") (pinfunction "PA0_6") (pintype "bidirectional"))
    )
    (net (code "51") (name "S01") (class "Default")
      (node (ref "F1") (pin "P$2") (pinfunction "E_P$2") (pintype "bidirectional"))
      (node (ref "X1") (pin "2") (pinfunction "2_2") (pintype "passive"))
    )
    (net (code "52") (name "S02") (class "Default")
      (node (ref "F2") (pin "P$2") (pinfunction "E_P$2") (pintype "bidirectional"))
      (node (ref "X1") (pin "1") (pinfunction "1_1") (pintype "passive"))
    )
    (net (code "53") (name "S2") (class "Default")
      (node (ref "U$21") (pin "P$3") (pinfunction "P$3_P$3") (pintype "bidirectional"))
      (node (ref "U$33") (pin "P$2") (pinfunction "P$2_P$2") (pintype "bidirectional"))
      (node (ref "U$47") (pin "P$1") (pinfunction "1_P$1") (pintype "bidirectional"))
      (node (ref "U2") (pin "7") (pinfunction "PA1_7") (pintype "bidirectional"))
    )
    (net (code "54") (name "S3") (class "Default")
      (node (ref "U$21") (pin "P$4") (pinfunction "P$4_P$4") (pintype "bidirectional"))
      (node (ref "U$34") (pin "P$2") (pinfunction "P$2_P$2") (pintype "bidirectional"))
      (node (ref "U$35") (pin "P$1") (pinfunction "1_P$1") (pintype "bidirectional"))
      (node (ref "U2") (pin "8") (pinfunction "PA2_8") (pintype "bidirectional"))
    )
    (net (code "55") (name "S03") (class "Default")
      (node (ref "F3") (pin "P$2") (pinfunction "E_P$2") (pintype "bidirectional"))
      (node (ref "X2") (pin "4") (pinfunction "4_4") (pintype "passive"))
    )
    (net (code "56") (name "S04") (class "Default")
      (node (ref "F4") (pin "P$2") (pinfunction "E_P$2") (pintype "bidirectional"))
      (node (ref "X2") (pin "3") (pinfunction "3_3") (pintype "passive"))
    )
    (net (code "57") (name "S4") (class "Default")
      (node (ref "U$21") (pin "P$5") (pinfunction "P$5_P$5") (pintype "bidirectional"))
      (node (ref "U$37") (pin "P$2") (pinfunction "P$2_P$2") (pintype "bidirectional"))
      (node (ref "U$38") (pin "P$1") (pinfunction "1_P$1") (pintype "bidirectional"))
      (node (ref "U2") (pin "9") (pinfunction "PA3_9") (pintype "bidirectional"))
    )
    (net (code "58") (name "S5") (class "Default")
      (node (ref "U$21") (pin "P$6") (pinfunction "P$6_P$6") (pintype "bidirectional"))
      (node (ref "U$44") (pin "P$2") (pinfunction "P$2_P$2") (pintype "bidirectional"))
      (node (ref "U$45") (pin "P$1") (pinfunction "1_P$1") (pintype "bidirectional"))
      (node (ref "U2") (pin "10") (pinfunction "PA4_10") (pintype "bidirectional"))
    )
    (net (code "59") (name "S05") (class "Default")
      (node (ref "F5") (pin "P$2") (pinfunction "E_P$2") (pintype "bidirectional"))
      (node (ref "X2") (pin "2") (pinfunction "2_2") (pintype "passive"))
    )
    (net (code "60") (name "S06") (class "Default")
      (node (ref "F6") (pin "P$2") (pinfunction "E_P$2") (pintype "bidirectional"))
      (node (ref "X2") (pin "1") (pinfunction "1_1") (pintype "passive"))
    )
    (net (code "61") (name "S6") (class "Default")
      (node (ref "U$21") (pin "P$7") (pinfunction "P$7_P$7") (pintype "bidirectional"))
      (node (ref "U$48") (pin "P$2") (pinfunction "P$2_P$2") (pintype "bidirectional"))
      (node (ref "U$49") (pin "P$1") (pinfunction "1_P$1") (pintype "bidirectional"))
      (node (ref "U2") (pin "11") (pinfunction "PA5_11") (pintype "bidirectional"))
    )
    (net (code "62") (name "SOLE") (class "Default")
      (node (ref "U$20") (pin "P$1") (pinfunction "P$1_P$1") (pintype "bidirectional"))
      (node (ref "U$22") (pin "P$1") (pinfunction "P$1_P$1") (pintype "bidirectional"))
      (node (ref "U2") (pin "13") (pinfunction "PA7_13") (pintype "bidirectional"))
    )
    (net (code "63") (name "SWO") (class "Default")
      (node (ref "SV2") (pin "6") (pinfunction "6_6") (pintype "passive"))
      (node (ref "U2") (pin "26") (pinfunction "PB3_26") (pintype "bidirectional"))
    )
    (net (code "64") (name "TCK") (class "Default")
      (node (ref "SV2") (pin "2") (pinfunction "2_2") (pintype "passive"))
      (node (ref "U2") (pin "24") (pinfunction "PA14_24") (pintype "bidirectional"))
    )
    (net (code "65") (name "TMS") (class "Default")
      (node (ref "SV2") (pin "4") (pinfunction "4_4") (pintype "passive"))
      (node (ref "U2") (pin "23") (pinfunction "PA13_23") (pintype "bidirectional"))
    )
    (net (code "66") (name "TX") (class "Default")
      (node (ref "U2") (pin "19") (pinfunction "PA9_19") (pintype "bidirectional"))
      (node (ref "X4") (pin "2") (pinfunction "2_2") (pintype "passive"))
    )
    (net (code "67") (name "unconnected-(U$67-P$3-PadP$2)") (class "Default")
      (node (ref "U$67") (pin "P$2") (pinfunction "P$3_P$2") (pintype "bidirectional"))
    )
    (net (code "68") (name "unconnected-(U2-PA6-Pad12)") (class "Default")
      (node (ref "U2") (pin "12") (pinfunction "PA6_12") (pintype "bidirectional"))
    )
    (net (code "69") (name "unconnected-(U2-PA15-Pad25)") (class "Default")
      (node (ref "U2") (pin "25") (pinfunction "PA15_25") (pintype "bidirectional"))
    )
  )
)
